# Volta-Interface-SCH_SH2__02.net
KiCad netlist of a schematic drawn in Altium Designer
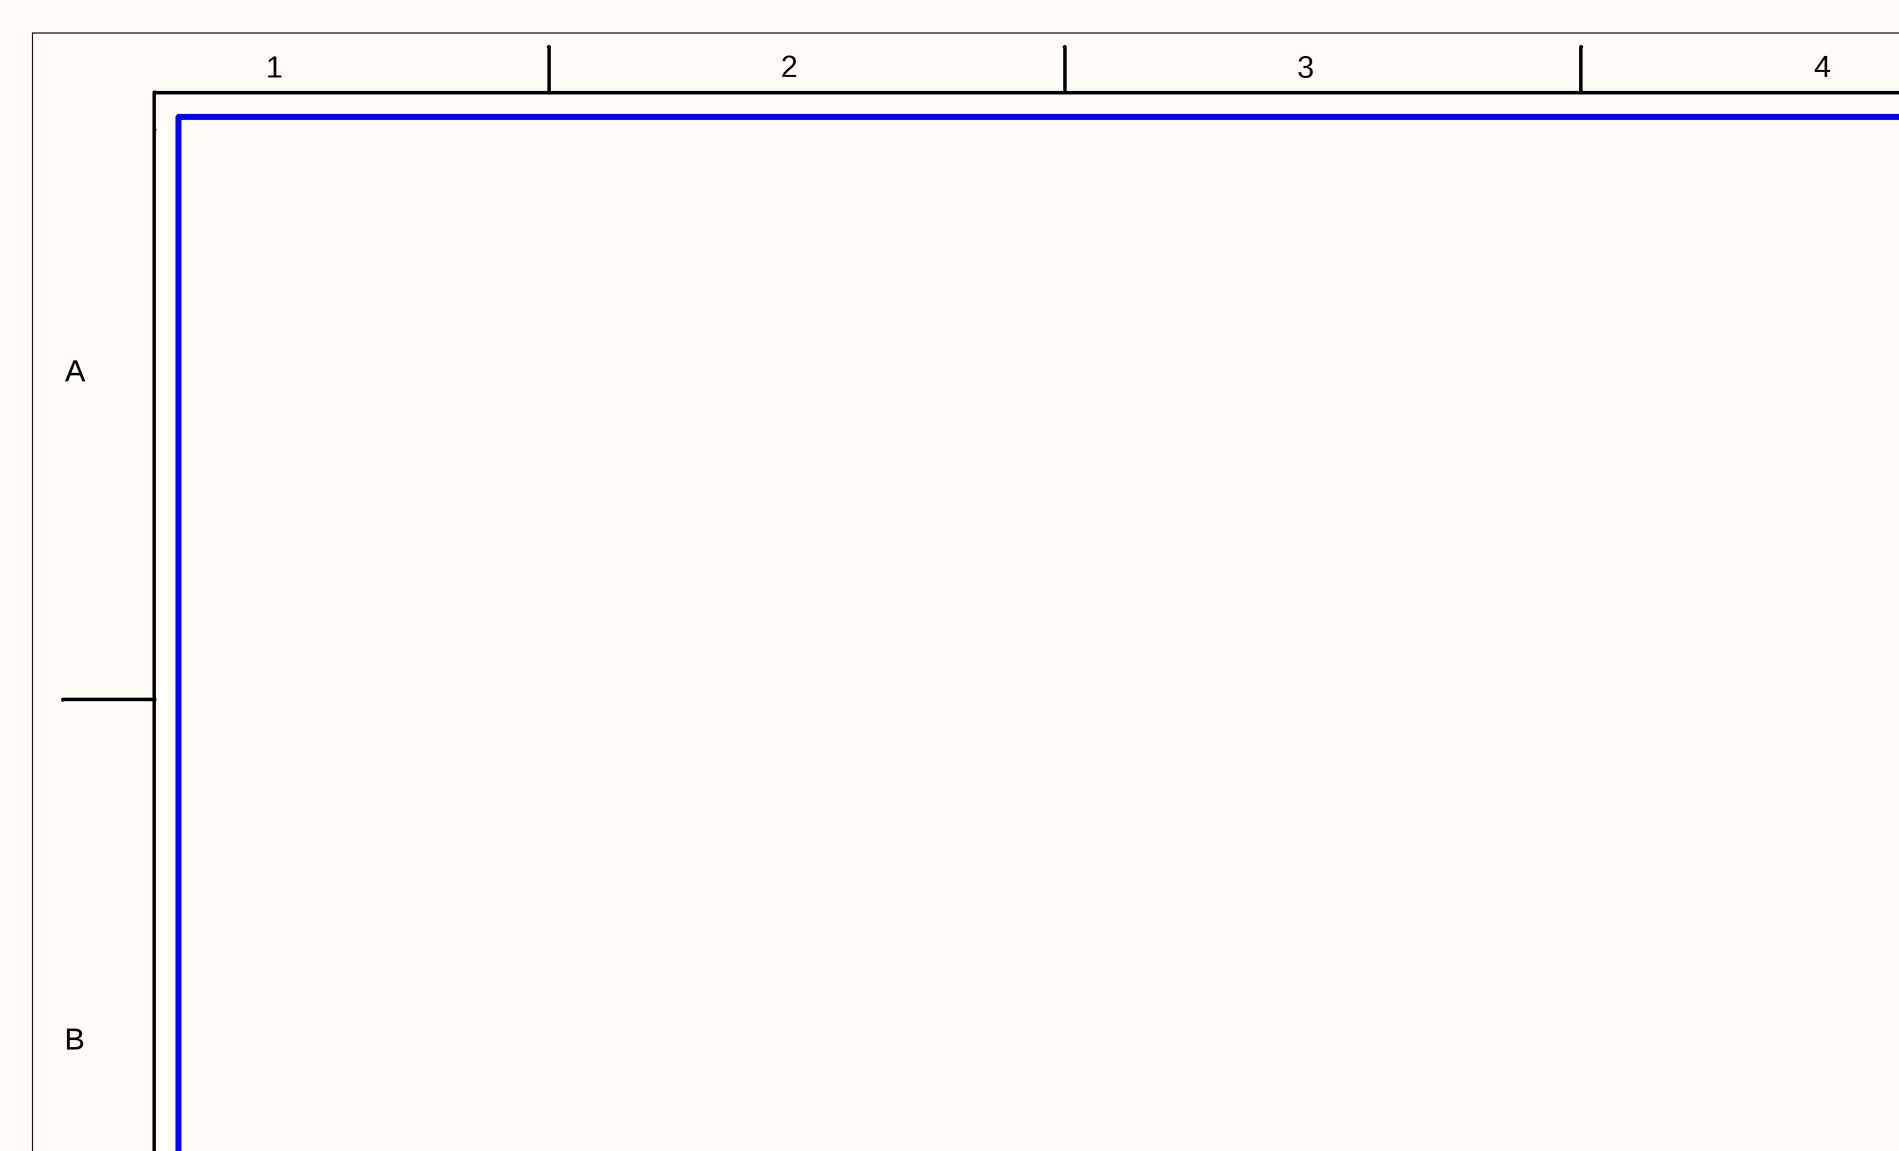
[diagram p0: Volta-Interface-SCH_SH2_(02).SchDoc, top left]
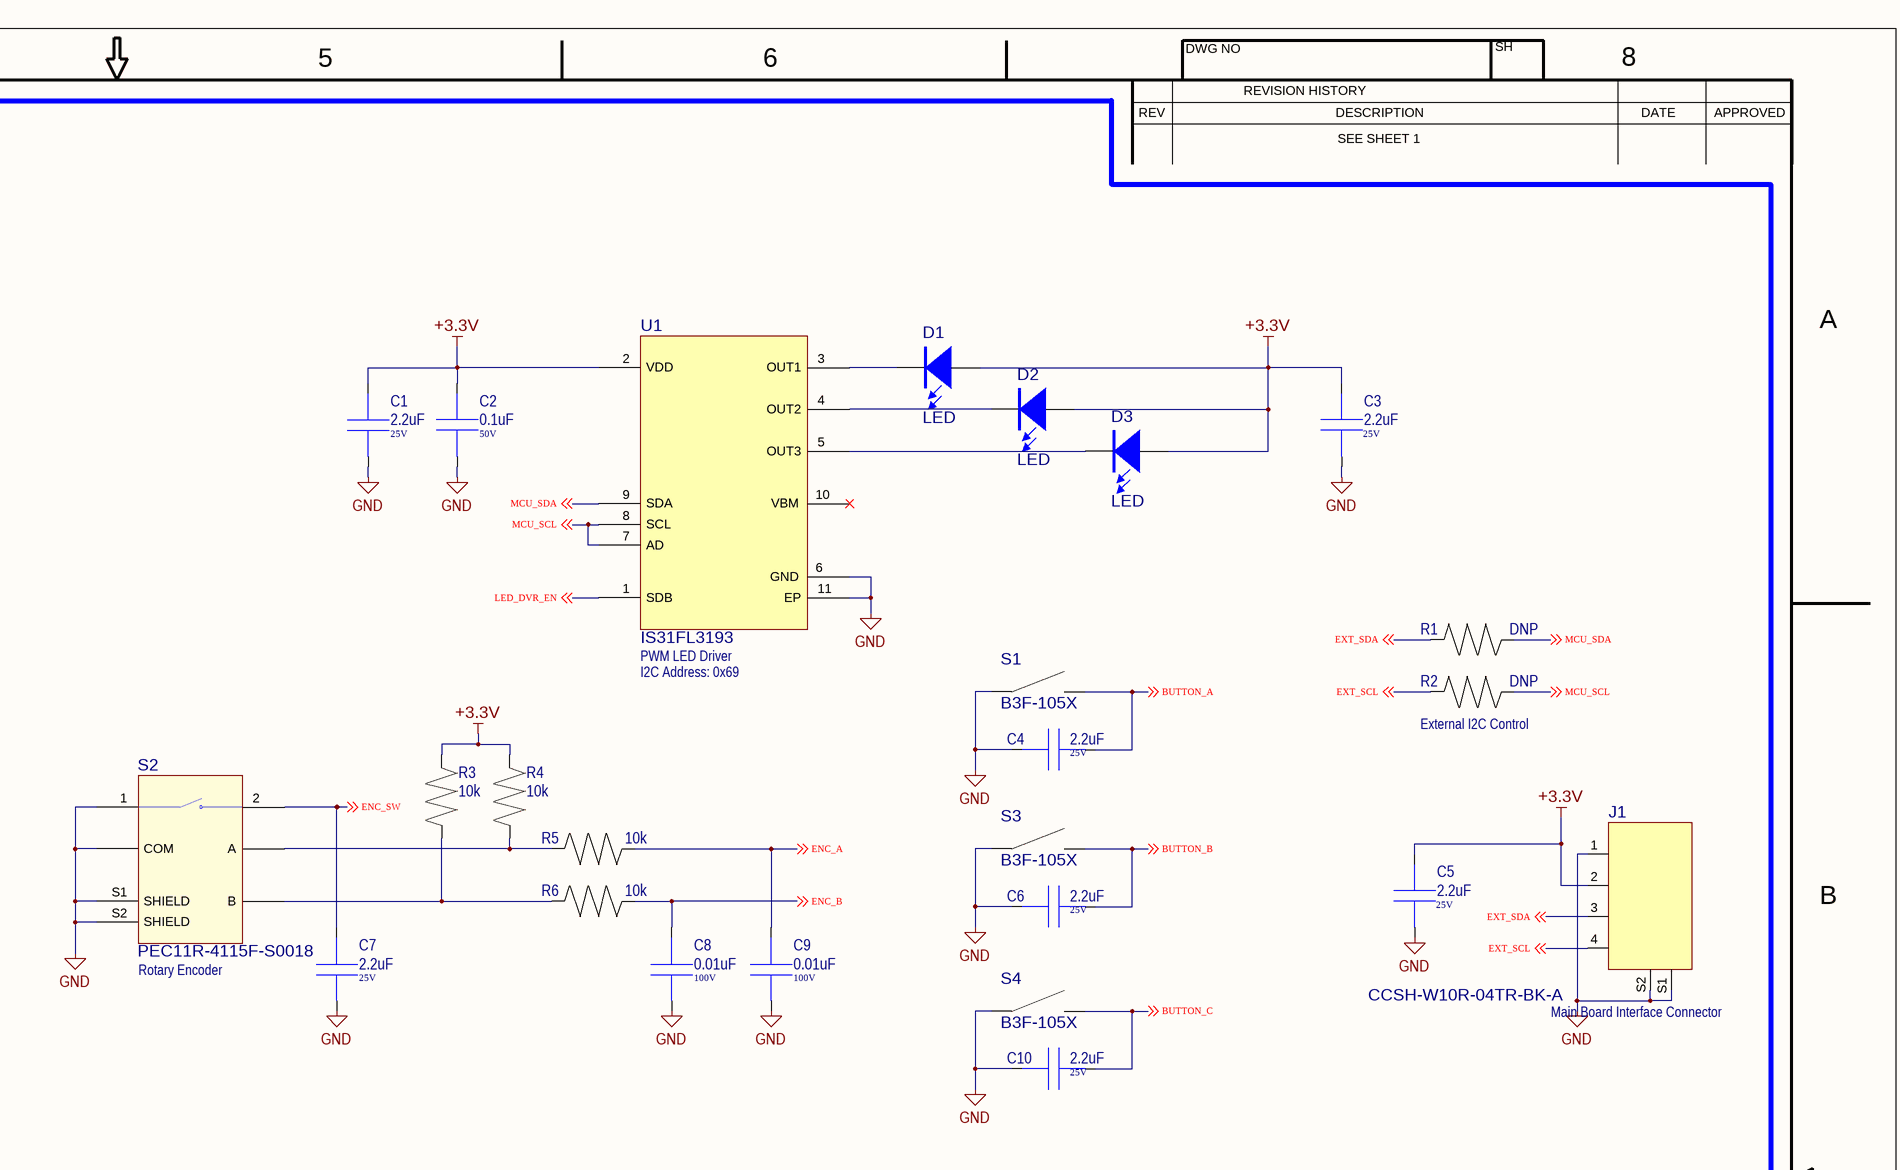
[diagram p1: Volta-Interface-SCH_SH2_(02).SchDoc, top right]
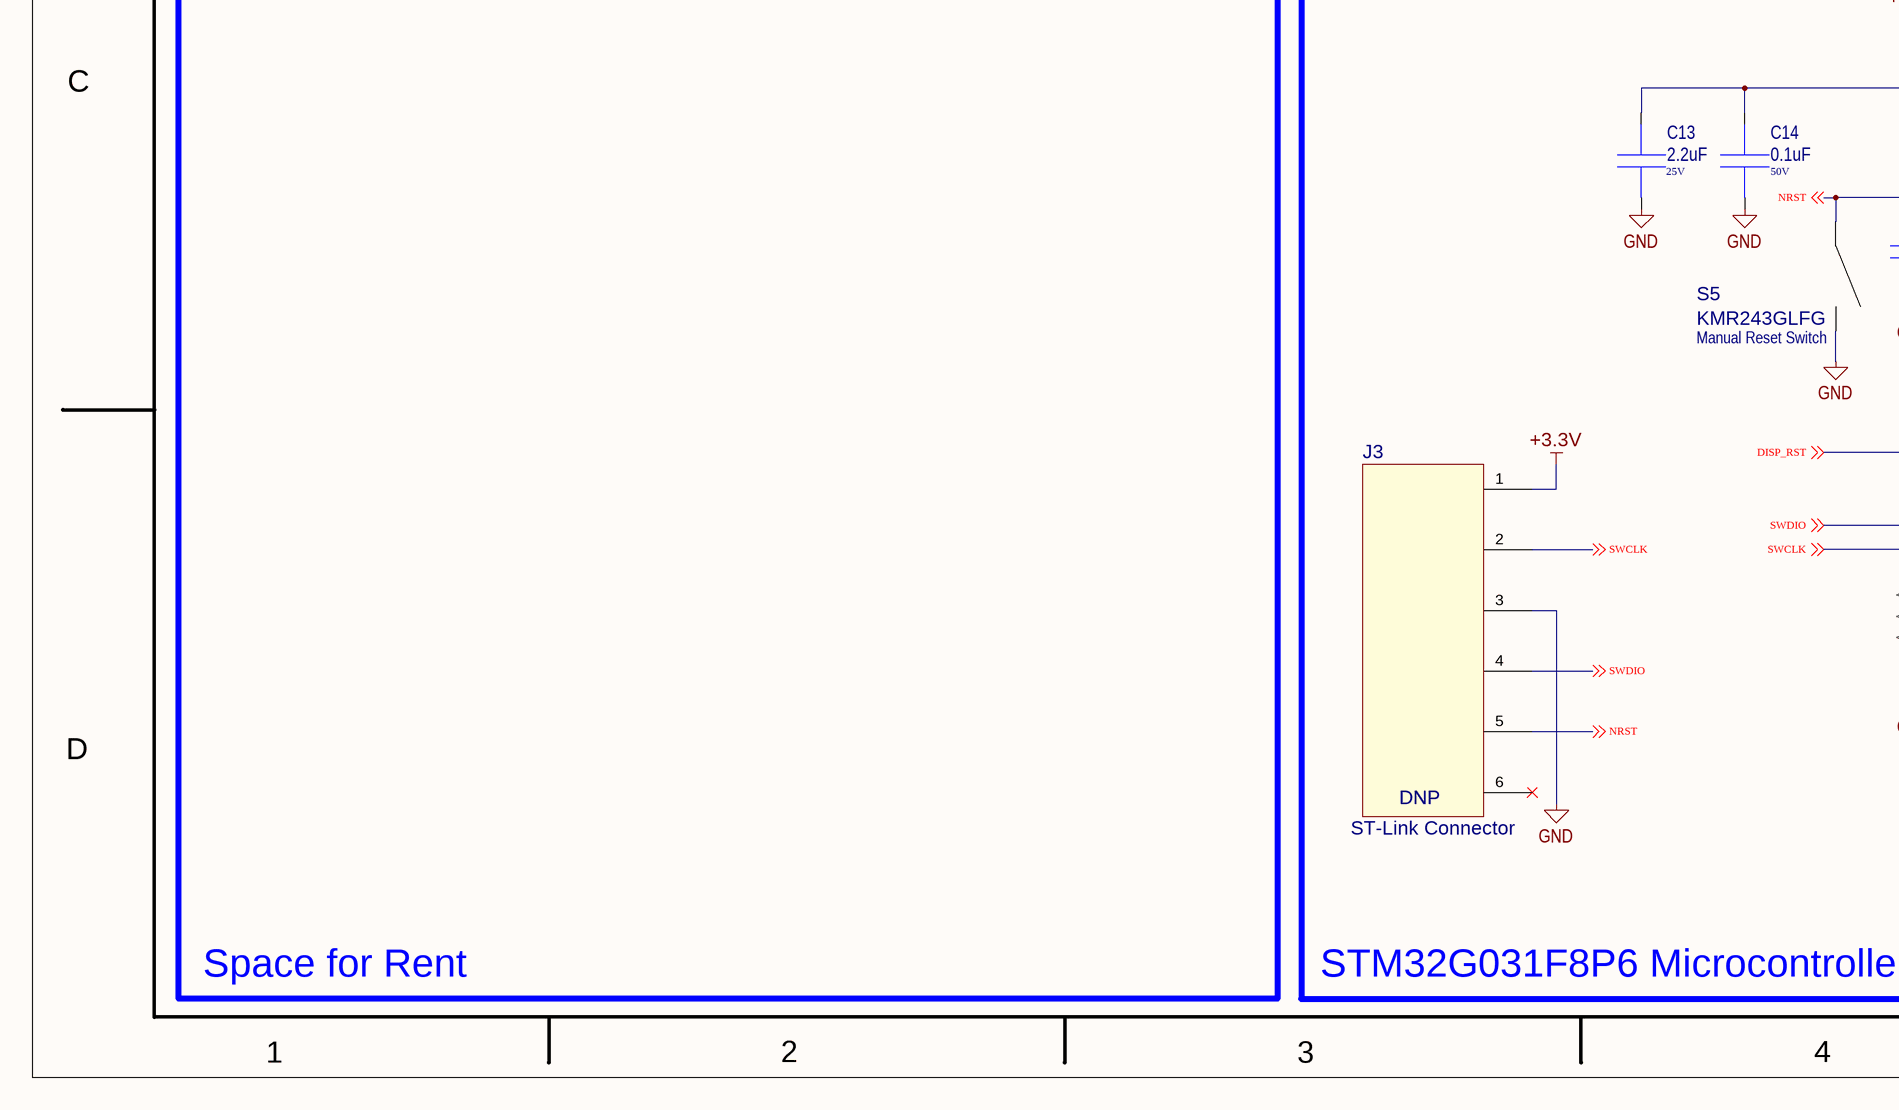
[diagram p2: Volta-Interface-SCH_SH2_(02).SchDoc, bottom left]
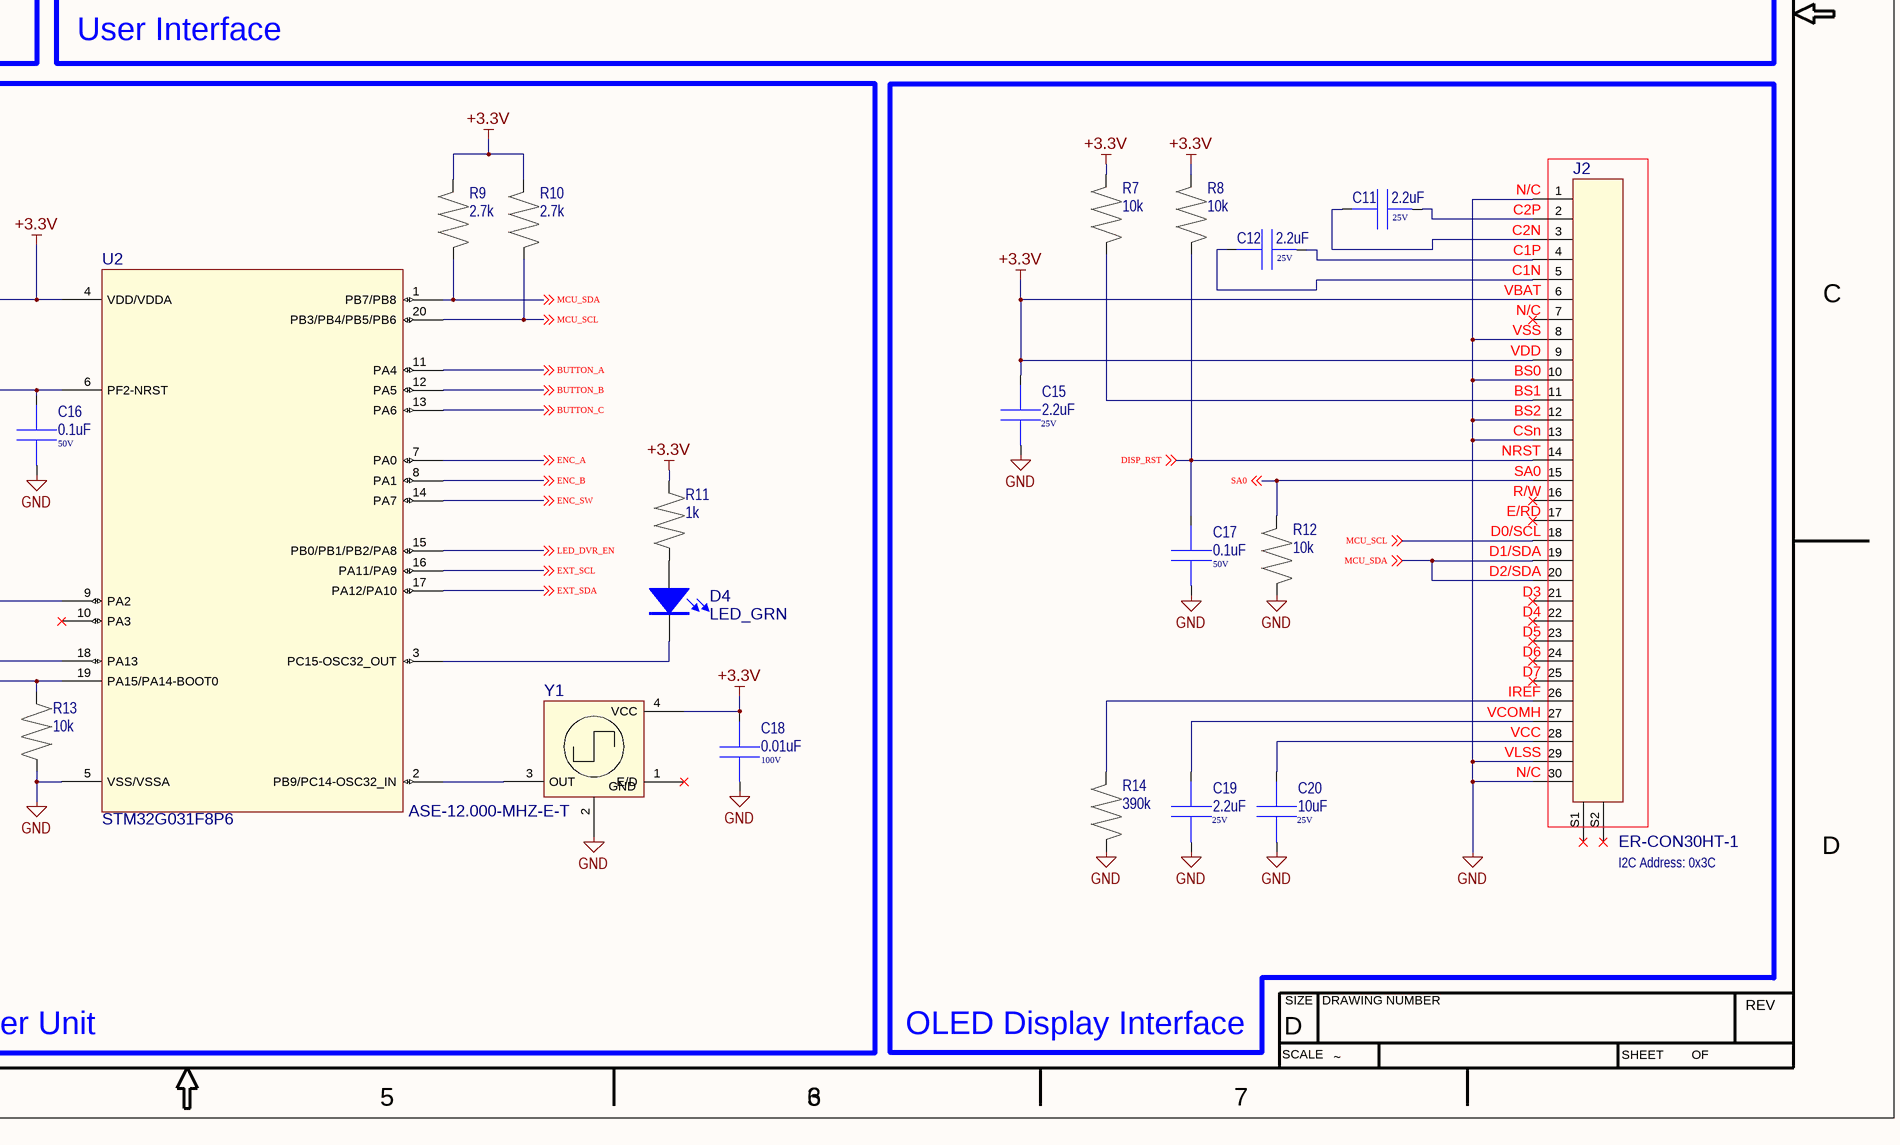
[diagram p3: Volta-Interface-SCH_SH2_(02).SchDoc, bottom right]

(export (version "E")
  (design (tool "Eeschema 10.0.6"))
  (components
    (comp (ref "C1")
      (value "2.2uF")
      (footprint "0402")
      (description "Multilayer Ceramic Capacitors MLCC - SMD/SMT 2.2UF 25V 10% 0402")
      (fields
        (field (name "PART NUMBER") "GRM155R61E225KE11D")
        (field (name "MANUFACTURER") "Murata Electronics")
        (field (name "VOLTAGE") "25V")
      )
      (libsource (lib "CAPACITORS") (part "CAP"))
    )
    (comp (ref "C2")
      (value "0.1uF")
      (footprint "0402")
      (description "CAP CER 0.1UF 50V X7R 0402")
      (fields
        (field (name "PART NUMBER") "UMK105B7104KVHF")
        (field (name "MANUFACTURER") "Taiyo Yuden")
        (field (name "VOLTAGE") "50V")
      )
      (libsource (lib "CAPACITORS") (part "CAP"))
    )
    (comp (ref "C3")
      (value "2.2uF")
      (footprint "0402")
      (description "Multilayer Ceramic Capacitors MLCC - SMD/SMT 2.2UF 25V 10% 0402")
      (fields
        (field (name "PART NUMBER") "GRM155R61E225KE11D")
        (field (name "MANUFACTURER") "Murata Electronics")
        (field (name "VOLTAGE") "25V")
      )
      (libsource (lib "CAPACITORS") (part "CAP"))
    )
    (comp (ref "C4")
      (value "2.2uF")
      (footprint "0402")
      (description "Multilayer Ceramic Capacitors MLCC - SMD/SMT 2.2UF 25V 10% 0402")
      (fields
        (field (name "PART NUMBER") "GRM155R61E225KE11D")
        (field (name "MANUFACTURER") "Murata Electronics")
        (field (name "VOLTAGE") "25V")
      )
      (libsource (lib "CAPACITORS") (part "CAP"))
    )
    (comp (ref "C5")
      (value "2.2uF")
      (footprint "0402")
      (description "Multilayer Ceramic Capacitors MLCC - SMD/SMT 2.2UF 25V 10% 0402")
      (fields
        (field (name "PART NUMBER") "GRM155R61E225KE11D")
        (field (name "MANUFACTURER") "Murata Electronics")
        (field (name "VOLTAGE") "25V")
      )
      (libsource (lib "CAPACITORS") (part "CAP"))
    )
    (comp (ref "C6")
      (value "2.2uF")
      (footprint "0402")
      (description "Multilayer Ceramic Capacitors MLCC - SMD/SMT 2.2UF 25V 10% 0402")
      (fields
        (field (name "PART NUMBER") "GRM155R61E225KE11D")
        (field (name "MANUFACTURER") "Murata Electronics")
        (field (name "VOLTAGE") "25V")
      )
      (libsource (lib "CAPACITORS") (part "CAP"))
    )
    (comp (ref "C7")
      (value "2.2uF")
      (footprint "0402")
      (description "Multilayer Ceramic Capacitors MLCC - SMD/SMT 2.2UF 25V 10% 0402")
      (fields
        (field (name "PART NUMBER") "GRM155R61E225KE11D")
        (field (name "MANUFACTURER") "Murata Electronics")
        (field (name "VOLTAGE") "25V")
      )
      (libsource (lib "CAPACITORS") (part "CAP"))
    )
    (comp (ref "C8")
      (value "0.01uF")
      (footprint "0402")
      (description "CAP CER 0.01UF 100V X7R 0402")
      (fields
        (field (name "PART NUMBER") "HMR105B7103MV-F")
        (field (name "MANUFACTURER") "Taiyo Yuden")
        (field (name "VOLTAGE") "100V")
      )
      (libsource (lib "CAPACITORS") (part "CAP"))
    )
    (comp (ref "C9")
      (value "0.01uF")
      (footprint "0402")
      (description "CAP CER 0.01UF 100V X7R 0402")
      (fields
        (field (name "PART NUMBER") "HMR105B7103MV-F")
        (field (name "MANUFACTURER") "Taiyo Yuden")
        (field (name "VOLTAGE") "100V")
      )
      (libsource (lib "CAPACITORS") (part "CAP"))
    )
    (comp (ref "C10")
      (value "2.2uF")
      (footprint "0402")
      (description "Multilayer Ceramic Capacitors MLCC - SMD/SMT 2.2UF 25V 10% 0402")
      (fields
        (field (name "PART NUMBER") "GRM155R61E225KE11D")
        (field (name "MANUFACTURER") "Murata Electronics")
        (field (name "VOLTAGE") "25V")
      )
      (libsource (lib "CAPACITORS") (part "CAP"))
    )
    (comp (ref "C11")
      (value "2.2uF")
      (footprint "0402")
      (description "CAP CER 10UF 10V X6S 0603")
      (fields
        (field (name "PART NUMBER") "GRM188C81A106MA73D")
        (field (name "MANUFACTURER") "Murata Electronics")
        (field (name "VOLTAGE") "25V")
      )
      (libsource (lib "CAPACITORS") (part "CAP"))
    )
    (comp (ref "C12")
      (value "2.2uF")
      (footprint "0402")
      (description "CAP CER 10UF 10V X6S 0603")
      (fields
        (field (name "PART NUMBER") "GRM188C81A106MA73D")
        (field (name "MANUFACTURER") "Murata Electronics")
        (field (name "VOLTAGE") "25V")
      )
      (libsource (lib "CAPACITORS") (part "CAP"))
    )
    (comp (ref "C13")
      (value "2.2uF")
      (footprint "0402")
      (description "Multilayer Ceramic Capacitors MLCC - SMD/SMT 2.2UF 25V 10% 0402")
      (fields
        (field (name "PART NUMBER") "GRM155R61E225KE11D")
        (field (name "MANUFACTURER") "Murata Electronics")
        (field (name "VOLTAGE") "25V")
      )
      (libsource (lib "CAPACITORS") (part "CAP"))
    )
    (comp (ref "C14")
      (value "0.1uF")
      (footprint "0402")
      (description "CAP CER 0.1UF 50V X7R 0402")
      (fields
        (field (name "PART NUMBER") "UMK105B7104KVHF")
        (field (name "MANUFACTURER") "Taiyo Yuden")
        (field (name "VOLTAGE") "50V")
      )
      (libsource (lib "CAPACITORS") (part "CAP"))
    )
    (comp (ref "C15")
      (value "2.2uF")
      (footprint "0402")
      (description "CAP CER 10UF 10V X6S 0603")
      (fields
        (field (name "PART NUMBER") "GRM188C81A106MA73D")
        (field (name "MANUFACTURER") "Murata Electronics")
        (field (name "VOLTAGE") "25V")
      )
      (libsource (lib "CAPACITORS") (part "CAP"))
    )
    (comp (ref "C16")
      (value "0.1uF")
      (footprint "0402")
      (description "CAP CER 0.1UF 50V X7R 0402")
      (fields
        (field (name "PART NUMBER") "UMK105B7104KVHF")
        (field (name "MANUFACTURER") "Taiyo Yuden")
        (field (name "VOLTAGE") "50V")
      )
      (libsource (lib "CAPACITORS") (part "CAP"))
    )
    (comp (ref "C17")
      (value "0.1uF")
      (footprint "0402")
      (description "CAP CER 0.1UF 50V X7R 0402")
      (fields
        (field (name "PART NUMBER") "UMK105B7104KVHF")
        (field (name "MANUFACTURER") "Taiyo Yuden")
        (field (name "VOLTAGE") "50V")
      )
      (libsource (lib "CAPACITORS") (part "CAP"))
    )
    (comp (ref "C18")
      (value "0.01uF")
      (footprint "0402")
      (description "CAP CER 0.01UF 100V X7R 0402")
      (fields
        (field (name "PART NUMBER") "HMR105B7103MV-F")
        (field (name "MANUFACTURER") "Taiyo Yuden")
        (field (name "VOLTAGE") "100V")
      )
      (libsource (lib "CAPACITORS") (part "CAP"))
    )
    (comp (ref "C19")
      (value "2.2uF")
      (footprint "0402")
      (description "CAP CER 10UF 10V X6S 0603")
      (fields
        (field (name "PART NUMBER") "GRM188C81A106MA73D")
        (field (name "MANUFACTURER") "Murata Electronics")
        (field (name "VOLTAGE") "25V")
      )
      (libsource (lib "CAPACITORS") (part "CAP"))
    )
    (comp (ref "C20")
      (value "10uF")
      (footprint "0402")
      (description "CAP CER 10UF 10V X6S 0603")
      (fields
        (field (name "PART NUMBER") "GRM188C81A106MA73D")
        (field (name "MANUFACTURER") "Murata Electronics")
        (field (name "VOLTAGE") "25V")
      )
      (libsource (lib "CAPACITORS") (part "CAP"))
    )
    (comp (ref "D1") (value "LED") (footprint "1206_LED") (libsource (lib "SEMICONDUCTORS") (part "LED")))
    (comp (ref "D2") (value "LED") (footprint "1206_LED") (libsource (lib "SEMICONDUCTORS") (part "LED")))
    (comp (ref "D3") (value "LED") (footprint "1206_LED") (libsource (lib "SEMICONDUCTORS") (part "LED")))
    (comp (ref "D4")
      (value "LED_GRN")
      (footprint "0603_LED_Red")
      (description "Standard LEDs - SMD HE Red 645 nm Water Clear")
      (fields (field (name "PART NUMBER") "SM0603HCL") (field (name "MANUFACTURER") "Bivar"))
      (libsource (lib "SEMICONDUCTORS") (part "LED_Red"))
    )
    (comp (ref "J1")
      (value "CCSH-W10R-04TR-BK-A")
      (footprint "PCBComponent_1")
      (fields (field (name "MANUFACTURER") "JST"))
      (libsource (lib "CCSH-W10R-04TR-BK-A") (part "CCSH-W10R-04TR-BK-A"))
    )
    (comp (ref "J2")
      (value "ER-CON30HT-1")
      (footprint "ER-CON30HT-1")
      (description "30 PINS 0.5 PITCH SMD TOP CONTACT CONN")
      (fields (field (name "MANUFACTURER") "EastRising Technology"))
      (libsource (lib "ER-CON30HT-1") (part "ER-CON30HT-1"))
    )
    (comp (ref "J3")
      (value "DNP")
      (footprint "801-93-006-10-012000")
      (description "CONN SOCKET STRIP LOPRO 6POS")
      (fields (field (name "MANUFACTURER") "Mill-Max") (field (name "PART NUMBER") "801-93-006-10-012000"))
      (libsource (lib "Connectors") (part "801-93-006-10-012000"))
    )
    (comp (ref "R1")
      (value "DNP")
      (footprint "0402")
      (description "Thick Film Resistors - SMD 1/16watt 0ohm Commercial Use")
      (fields (field (name "PART NUMBER") "CRCW04020000Z0EDC") (field (name "MANUFACTURER") "Vishay / Dale"))
      (libsource (lib "RESISTORS") (part "RES"))
    )
    (comp (ref "R2")
      (value "DNP")
      (footprint "0402")
      (description "Thick Film Resistors - SMD 1/16watt 0ohm Commercial Use")
      (fields (field (name "PART NUMBER") "CRCW04020000Z0EDC") (field (name "MANUFACTURER") "Vishay / Dale"))
      (libsource (lib "RESISTORS") (part "RES"))
    )
    (comp (ref "R3")
      (value "10k")
      (footprint "0402")
      (description "Thick Film Resistors - SMD 10K OHM 1%")
      (fields (field (name "PART NUMBER") "CR0402-FX-1002GLF") (field (name "MANUFACTURER") "Bourns"))
      (libsource (lib "RESISTORS") (part "RES"))
    )
    (comp (ref "R4")
      (value "10k")
      (footprint "0402")
      (description "Thick Film Resistors - SMD 10K OHM 1%")
      (fields (field (name "PART NUMBER") "CR0402-FX-1002GLF") (field (name "MANUFACTURER") "Bourns"))
      (libsource (lib "RESISTORS") (part "RES"))
    )
    (comp (ref "R5")
      (value "10k")
      (footprint "0402")
      (description "Thick Film Resistors - SMD 10K OHM 1%")
      (fields (field (name "PART NUMBER") "CR0402-FX-1002GLF") (field (name "MANUFACTURER") "Bourns"))
      (libsource (lib "RESISTORS") (part "RES"))
    )
    (comp (ref "R6")
      (value "10k")
      (footprint "0402")
      (description "Thick Film Resistors - SMD 10K OHM 1%")
      (fields (field (name "PART NUMBER") "CR0402-FX-1002GLF") (field (name "MANUFACTURER") "Bourns"))
      (libsource (lib "RESISTORS") (part "RES"))
    )
    (comp (ref "R7")
      (value "10k")
      (footprint "0402")
      (description "Thick Film Resistors - SMD 0603 5.1Kohm 5% High Voltage")
      (fields (field (name "PART NUMBER") "KTR03EZPJ512") (field (name "MANUFACTURER") "ROHM Semiconductor"))
      (libsource (lib "RESISTORS") (part "RES"))
    )
    (comp (ref "R8")
      (value "10k")
      (footprint "0402")
      (description "Thick Film Resistors - SMD 0603 5.1Kohm 5% High Voltage")
      (fields (field (name "PART NUMBER") "KTR03EZPJ512") (field (name "MANUFACTURER") "ROHM Semiconductor"))
      (libsource (lib "RESISTORS") (part "RES"))
    )
    (comp (ref "R9")
      (value "2.7k")
      (footprint "0402")
      (description "Thick Film Resistors - SMD 0402 2.7Kohms 1% AEC-Q200")
      (fields (field (name "PART NUMBER") "ERJ-2RKF2701X") (field (name "MANUFACTURER") "Panasonic"))
      (libsource (lib "RESISTORS") (part "RES"))
    )
    (comp (ref "R10")
      (value "2.7k")
      (footprint "0402")
      (description "Thick Film Resistors - SMD 0402 2.7Kohms 1% AEC-Q200")
      (fields (field (name "PART NUMBER") "ERJ-2RKF2701X") (field (name "MANUFACTURER") "Panasonic"))
      (libsource (lib "RESISTORS") (part "RES"))
    )
    (comp (ref "R11")
      (value "1k")
      (footprint "0402")
      (description "Thick Film Resistors - SMD ResA 0402 1k 1% 63mW TC100")
      (fields (field (name "PART NUMBER") "CR0402AFX-1001GLF") (field (name "MANUFACTURER") "Bourns"))
      (libsource (lib "RESISTORS") (part "RES"))
    )
    (comp (ref "R12")
      (value "10k")
      (footprint "0402")
      (description "Thick Film Resistors - SMD 0603 5.1Kohm 5% High Voltage")
      (fields (field (name "PART NUMBER") "KTR03EZPJ512") (field (name "MANUFACTURER") "ROHM Semiconductor"))
      (libsource (lib "RESISTORS") (part "RES"))
    )
    (comp (ref "R13")
      (value "10k")
      (footprint "0402")
      (description "Thick Film Resistors - SMD 10K OHM 1%")
      (fields (field (name "PART NUMBER") "CR0402-FX-1002GLF") (field (name "MANUFACTURER") "Bourns"))
      (libsource (lib "RESISTORS") (part "RES"))
    )
    (comp (ref "R14")
      (value "390k")
      (footprint "0402")
      (description "Thick Film Resistors - SMD 0603 5.1Kohm 5% High Voltage")
      (fields (field (name "PART NUMBER") "KTR03EZPJ512") (field (name "MANUFACTURER") "ROHM Semiconductor"))
      (libsource (lib "RESISTORS") (part "RES"))
    )
    (comp (ref "S1")
      (value "B3F-105X")
      (footprint "B3F-105X")
      (description "SWITCH TACTILE SPST-NO 0.05A 24V")
      (fields (field (name "MANUFACTURER") "Omron Electronics Inc-EMC Div"))
      (libsource (lib "B3F-105X") (part "B3F-105X"))
    )
    (comp (ref "S2")
      (value "PEC11R-4115F-S0018")
      (footprint "PEC11R-4xxxF-Sxxxx")
      (description "ROTARY ENCODER MECHANICAL XXPPR")
      (fields (field (name "MANUFACTURER") "Bourns"))
      (libsource (lib "PEC11R-4xxxF-Sxxxx") (part "PEC11R-4xxxF-Sxxxx"))
    )
    (comp (ref "S3")
      (value "B3F-105X")
      (footprint "B3F-105X")
      (description "SWITCH TACTILE SPST-NO 0.05A 24V")
      (fields (field (name "MANUFACTURER") "Omron Electronics Inc-EMC Div"))
      (libsource (lib "B3F-105X") (part "B3F-105X"))
    )
    (comp (ref "S4")
      (value "B3F-105X")
      (footprint "B3F-105X")
      (description "SWITCH TACTILE SPST-NO 0.05A 24V")
      (fields (field (name "MANUFACTURER") "Omron Electronics Inc-EMC Div"))
      (libsource (lib "B3F-105X") (part "B3F-105X"))
    )
    (comp (ref "S5")
      (value "KMR243GLFG")
      (footprint "KMR 2 Series")
      (description "Tactile Switch SPST-NO Top Actuated Surface Mount")
      (fields (field (name "MANUFACTURER") "C&K") (field (name "PART NUMBER") "KMR243GFLG"))
      (libsource (lib "KMR2 Series") (part "KMR 2 Series"))
    )
    (comp (ref "U1")
      (value "IS31FL3193")
      (footprint "DFN-10")
      (description "IC LED DRIVER LINEAR 42MA 10DFN")
      (fields
        (field (name "MANUFACTURER") "Lumissil Microsystems")
        (field (name "PART NUMBER") "IS31FL3193-DLS2-TR")
      )
      (libsource (lib "IS31FL3193") (part "IS31FL3193"))
    )
    (comp (ref "U2")
      (value "STM32G031F8P6")
      (footprint "TSSOP-20")
      (description "IC MCU 32BIT 64KB FLASH 20TSSOP")
      (fields (field (name "MANUFACTURER") "STMicroelectronics"))
      (libsource (lib "STM32G031Fxxx") (part "STM32G031F6P6"))
    )
    (comp (ref "Y1")
      (value "ASE-12.000-MHZ-E-T")
      (footprint "ASE-XXXXX-X-X-X")
      (description "OSC XO 12.000MHZ CMOS SMD")
      (fields (field (name "MANUFACTURER") "Abracon"))
      (libsource (lib "Oscillators") (part "ASE-XXXXX-MHZ-X-X"))
    )
  )
  (nets
    (net (code "1") (name "+3.3V") (class "Default")
      (node (ref "C1") (pin "2") (pinfunction "2_2") (pintype "passive"))
      (node (ref "C13") (pin "2") (pinfunction "2_2") (pintype "passive"))
      (node (ref "C14") (pin "2") (pinfunction "2_2") (pintype "passive"))
      (node (ref "C15") (pin "2") (pinfunction "2_2") (pintype "passive"))
      (node (ref "C18") (pin "2") (pinfunction "2_2") (pintype "passive"))
      (node (ref "C2") (pin "2") (pinfunction "2_2") (pintype "passive"))
      (node (ref "C3") (pin "2") (pinfunction "2_2") (pintype "passive"))
      (node (ref "C5") (pin "2") (pinfunction "2_2") (pintype "passive"))
      (node (ref "D1") (pin "1") (pinfunction "A_1") (pintype "passive"))
      (node (ref "D2") (pin "1") (pinfunction "A_1") (pintype "passive"))
      (node (ref "D3") (pin "1") (pinfunction "A_1") (pintype "passive"))
      (node (ref "J1") (pin "2") (pinfunction "2_2") (pintype "passive"))
      (node (ref "J2") (pin "6") (pinfunction "6_6") (pintype "passive"))
      (node (ref "J2") (pin "9") (pinfunction "9_9") (pintype "passive"))
      (node (ref "J3") (pin "1") (pinfunction "1_1") (pintype "passive"))
      (node (ref "R10") (pin "2") (pinfunction "2_2") (pintype "passive"))
      (node (ref "R11") (pin "2") (pinfunction "2_2") (pintype "passive"))
      (node (ref "R3") (pin "1") (pinfunction "1_1") (pintype "passive"))
      (node (ref "R4") (pin "1") (pinfunction "1_1") (pintype "passive"))
      (node (ref "R7") (pin "2") (pinfunction "2_2") (pintype "passive"))
      (node (ref "R8") (pin "2") (pinfunction "2_2") (pintype "passive"))
      (node (ref "R9") (pin "2") (pinfunction "2_2") (pintype "passive"))
      (node (ref "U1") (pin "2") (pinfunction "VDD_2") (pintype "passive"))
      (node (ref "U2") (pin "4") (pinfunction "VDD/VDDA_4") (pintype "power_in"))
      (node (ref "Y1") (pin "4") (pinfunction "VCC_4") (pintype "power_in"))
    )
    (net (code "2") (name "BUTTON_A") (class "Default")
      (node (ref "C4") (pin "1") (pinfunction "1_1") (pintype "passive"))
      (node (ref "S1") (pin "2") (pinfunction "2_2") (pintype "passive"))
      (node (ref "U2") (pin "11") (pinfunction "PA4_11") (pintype "bidirectional"))
    )
    (net (code "3") (name "BUTTON_B") (class "Default")
      (node (ref "C6") (pin "1") (pinfunction "1_1") (pintype "passive"))
      (node (ref "S3") (pin "2") (pinfunction "2_2") (pintype "passive"))
      (node (ref "U2") (pin "12") (pinfunction "PA5_12") (pintype "bidirectional"))
    )
    (net (code "4") (name "BUTTON_C") (class "Default")
      (node (ref "C10") (pin "1") (pinfunction "1_1") (pintype "passive"))
      (node (ref "S4") (pin "2") (pinfunction "2_2") (pintype "passive"))
      (node (ref "U2") (pin "13") (pinfunction "PA6_13") (pintype "bidirectional"))
    )
    (net (code "5") (name "DISP_RST") (class "Default")
      (node (ref "C17") (pin "2") (pinfunction "2_2") (pintype "passive"))
      (node (ref "J2") (pin "14") (pinfunction "14_14") (pintype "passive"))
      (node (ref "R8") (pin "1") (pinfunction "1_1") (pintype "passive"))
      (node (ref "U2") (pin "9") (pinfunction "PA2_9") (pintype "bidirectional"))
    )
    (net (code "6") (name "ENC_A") (class "Default")
      (node (ref "C9") (pin "2") (pinfunction "2_2") (pintype "passive"))
      (node (ref "R5") (pin "2") (pinfunction "2_2") (pintype "passive"))
      (node (ref "U2") (pin "7") (pinfunction "PA0_7") (pintype "bidirectional"))
    )
    (net (code "7") (name "ENC_B") (class "Default")
      (node (ref "C8") (pin "2") (pinfunction "2_2") (pintype "passive"))
      (node (ref "R6") (pin "2") (pinfunction "2_2") (pintype "passive"))
      (node (ref "U2") (pin "8") (pinfunction "PA1_8") (pintype "bidirectional"))
    )
    (net (code "8") (name "ENC_SW") (class "Default")
      (node (ref "C7") (pin "2") (pinfunction "2_2") (pintype "passive"))
      (node (ref "S2") (pin "2") (pinfunction "2_2") (pintype "passive"))
      (node (ref "U2") (pin "14") (pinfunction "PA7_14") (pintype "bidirectional"))
    )
    (net (code "9") (name "EXT_SCL") (class "Default")
      (node (ref "J1") (pin "4") (pinfunction "4_4") (pintype "passive"))
      (node (ref "R2") (pin "2") (pinfunction "2_2") (pintype "passive"))
      (node (ref "U2") (pin "16") (pinfunction "PA11/PA9_16") (pintype "bidirectional"))
    )
    (net (code "10") (name "EXT_SDA") (class "Default")
      (node (ref "J1") (pin "3") (pinfunction "3_3") (pintype "passive"))
      (node (ref "R1") (pin "2") (pinfunction "2_2") (pintype "passive"))
      (node (ref "U2") (pin "17") (pinfunction "PA12/PA10_17") (pintype "bidirectional"))
    )
    (net (code "11") (name "GND") (class "Default")
      (node (ref "C1") (pin "1") (pinfunction "1_1") (pintype "passive"))
      (node (ref "C10") (pin "2") (pinfunction "2_2") (pintype "passive"))
      (node (ref "C13") (pin "1") (pinfunction "1_1") (pintype "passive"))
      (node (ref "C14") (pin "1") (pinfunction "1_1") (pintype "passive"))
      (node (ref "C15") (pin "1") (pinfunction "1_1") (pintype "passive"))
      (node (ref "C16") (pin "1") (pinfunction "1_1") (pintype "passive"))
      (node (ref "C17") (pin "1") (pinfunction "1_1") (pintype "passive"))
      (node (ref "C18") (pin "1") (pinfunction "1_1") (pintype "passive"))
      (node (ref "C19") (pin "1") (pinfunction "1_1") (pintype "passive"))
      (node (ref "C2") (pin "1") (pinfunction "1_1") (pintype "passive"))
      (node (ref "C20") (pin "1") (pinfunction "1_1") (pintype "passive"))
      (node (ref "C3") (pin "1") (pinfunction "1_1") (pintype "passive"))
      (node (ref "C4") (pin "2") (pinfunction "2_2") (pintype "passive"))
      (node (ref "C5") (pin "1") (pinfunction "1_1") (pintype "passive"))
      (node (ref "C6") (pin "2") (pinfunction "2_2") (pintype "passive"))
      (node (ref "C7") (pin "1") (pinfunction "1_1") (pintype "passive"))
      (node (ref "C8") (pin "1") (pinfunction "1_1") (pintype "passive"))
      (node (ref "C9") (pin "1") (pinfunction "1_1") (pintype "passive"))
      (node (ref "J1") (pin "1") (pinfunction "1_1") (pintype "passive"))
      (node (ref "J1") (pin "S1") (pinfunction "S1_S1") (pintype "passive"))
      (node (ref "J1") (pin "S2") (pinfunction "S2_S2") (pintype "passive"))
      (node (ref "J2") (pin "1") (pinfunction "1_1") (pintype "passive"))
      (node (ref "J2") (pin "10") (pinfunction "10_10") (pintype "passive"))
      (node (ref "J2") (pin "12") (pinfunction "12_12") (pintype "passive"))
      (node (ref "J2") (pin "13") (pinfunction "13_13") (pintype "passive"))
      (node (ref "J2") (pin "29") (pinfunction "29_29") (pintype "passive"))
      (node (ref "J2") (pin "30") (pinfunction "30_30") (pintype "passive"))
      (node (ref "J2") (pin "8") (pinfunction "8_8") (pintype "passive"))
      (node (ref "J3") (pin "3") (pinfunction "3_3") (pintype "passive"))
      (node (ref "R12") (pin "1") (pinfunction "1_1") (pintype "passive"))
      (node (ref "R13") (pin "2") (pinfunction "2_2") (pintype "passive"))
      (node (ref "R14") (pin "1") (pinfunction "1_1") (pintype "passive"))
      (node (ref "S1") (pin "1") (pinfunction "1_1") (pintype "passive"))
      (node (ref "S2") (pin "1") (pinfunction "1_1") (pintype "passive"))
      (node (ref "S2") (pin "COM") (pinfunction "COM_COM") (pintype "passive"))
      (node (ref "S2") (pin "S1") (pinfunction "SHIELD_S1") (pintype "passive"))
      (node (ref "S2") (pin "S2") (pinfunction "SHIELD_S2") (pintype "passive"))
      (node (ref "S3") (pin "1") (pinfunction "1_1") (pintype "passive"))
      (node (ref "S4") (pin "1") (pinfunction "1_1") (pintype "passive"))
      (node (ref "S5") (pin "2") (pinfunction "2_2") (pintype "passive"))
      (node (ref "U1") (pin "11") (pinfunction "EP_11") (pintype "passive"))
      (node (ref "U1") (pin "6") (pinfunction "GND_6") (pintype "passive"))
      (node (ref "U2") (pin "5") (pinfunction "VSS/VSSA_5") (pintype "power_in"))
      (node (ref "Y1") (pin "2") (pinfunction "GND_2") (pintype "passive"))
    )
    (net (code "12") (name "LED_DVR_EN") (class "Default")
      (node (ref "U1") (pin "1") (pinfunction "SDB_1") (pintype "passive"))
      (node (ref "U2") (pin "15") (pinfunction "PB0/PB1/PB2/PA8_15") (pintype "bidirectional"))
    )
    (net (code "13") (name "MCU_SCL") (class "Default")
      (node (ref "J2") (pin "18") (pinfunction "18_18") (pintype "passive"))
      (node (ref "R10") (pin "1") (pinfunction "1_1") (pintype "passive"))
      (node (ref "R2") (pin "1") (pinfunction "1_1") (pintype "passive"))
      (node (ref "U1") (pin "7") (pinfunction "AD_7") (pintype "passive"))
      (node (ref "U1") (pin "8") (pinfunction "SCL_8") (pintype "passive"))
      (node (ref "U2") (pin "20") (pinfunction "PB3/PB4/PB5/PB6_20") (pintype "bidirectional"))
    )
    (net (code "14") (name "MCU_SDA") (class "Default")
      (node (ref "J2") (pin "19") (pinfunction "19_19") (pintype "passive"))
      (node (ref "J2") (pin "20") (pinfunction "20_20") (pintype "passive"))
      (node (ref "R1") (pin "1") (pinfunction "1_1") (pintype "passive"))
      (node (ref "R9") (pin "1") (pinfunction "1_1") (pintype "passive"))
      (node (ref "U1") (pin "9") (pinfunction "SDA_9") (pintype "passive"))
      (node (ref "U2") (pin "1") (pinfunction "PB7/PB8_1") (pintype "bidirectional"))
    )
    (net (code "15") (name "NRST") (class "Default")
      (node (ref "C16") (pin "2") (pinfunction "2_2") (pintype "passive"))
      (node (ref "J3") (pin "5") (pinfunction "5_5") (pintype "passive"))
      (node (ref "S5") (pin "1") (pinfunction "1_1") (pintype "passive"))
      (node (ref "U2") (pin "6") (pinfunction "PF2-NRST_6") (pintype "passive"))
    )
    (net (code "16") (name "Net-(C11-Pad1)") (class "Default")
      (node (ref "C11") (pin "1") (pinfunction "1_1") (pintype "passive"))
      (node (ref "J2") (pin "2") (pinfunction "2_2") (pintype "passive"))
    )
    (net (code "17") (name "Net-(C11-Pad2)") (class "Default")
      (node (ref "C11") (pin "2") (pinfunction "2_2") (pintype "passive"))
      (node (ref "J2") (pin "3") (pinfunction "3_3") (pintype "passive"))
    )
    (net (code "18") (name "Net-(C12-Pad1)") (class "Default")
      (node (ref "C12") (pin "1") (pinfunction "1_1") (pintype "passive"))
      (node (ref "J2") (pin "4") (pinfunction "4_4") (pintype "passive"))
    )
    (net (code "19") (name "Net-(C12-Pad2)") (class "Default")
      (node (ref "C12") (pin "2") (pinfunction "2_2") (pintype "passive"))
      (node (ref "J2") (pin "5") (pinfunction "5_5") (pintype "passive"))
    )
    (net (code "20") (name "Net-(C19-Pad2)") (class "Default")
      (node (ref "C19") (pin "2") (pinfunction "2_2") (pintype "passive"))
      (node (ref "J2") (pin "27") (pinfunction "27_27") (pintype "passive"))
    )
    (net (code "21") (name "Net-(C20-Pad2)") (class "Default")
      (node (ref "C20") (pin "2") (pinfunction "2_2") (pintype "passive"))
      (node (ref "J2") (pin "28") (pinfunction "28_28") (pintype "passive"))
    )
    (net (code "22") (name "Net-(D1-K)") (class "Default")
      (node (ref "D1") (pin "2") (pinfunction "K_2") (pintype "passive"))
      (node (ref "U1") (pin "3") (pinfunction "OUT1_3") (pintype "passive"))
    )
    (net (code "23") (name "Net-(D2-K)") (class "Default")
      (node (ref "D2") (pin "2") (pinfunction "K_2") (pintype "passive"))
      (node (ref "U1") (pin "4") (pinfunction "OUT2_4") (pintype "passive"))
    )
    (net (code "24") (name "Net-(D3-K)") (class "Default")
      (node (ref "D3") (pin "2") (pinfunction "K_2") (pintype "passive"))
      (node (ref "U1") (pin "5") (pinfunction "OUT3_5") (pintype "passive"))
    )
    (net (code "25") (name "Net-(D4-A)") (class "Default")
      (node (ref "D4") (pin "1") (pinfunction "A_1") (pintype "passive"))
      (node (ref "R11") (pin "1") (pinfunction "1_1") (pintype "passive"))
    )
    (net (code "26") (name "Net-(D4-K)") (class "Default")
      (node (ref "D4") (pin "2") (pinfunction "K_2") (pintype "passive"))
      (node (ref "U2") (pin "3") (pinfunction "PC15-OSC32_OUT_3") (pintype "bidirectional"))
    )
    (net (code "27") (name "Net-(J2-Pad11)") (class "Default")
      (node (ref "J2") (pin "11") (pinfunction "11_11") (pintype "passive"))
      (node (ref "R7") (pin "1") (pinfunction "1_1") (pintype "passive"))
    )
    (net (code "28") (name "Net-(J2-Pad26)") (class "Default")
      (node (ref "J2") (pin "26") (pinfunction "26_26") (pintype "passive"))
      (node (ref "R14") (pin "2") (pinfunction "2_2") (pintype "passive"))
    )
    (net (code "29") (name "Net-(R3-Pad2)") (class "Default")
      (node (ref "R3") (pin "2") (pinfunction "2_2") (pintype "passive"))
      (node (ref "R6") (pin "1") (pinfunction "1_1") (pintype "passive"))
      (node (ref "S2") (pin "B") (pinfunction "B_B") (pintype "passive"))
    )
    (net (code "30") (name "Net-(R4-Pad2)") (class "Default")
      (node (ref "R4") (pin "2") (pinfunction "2_2") (pintype "passive"))
      (node (ref "R5") (pin "1") (pinfunction "1_1") (pintype "passive"))
      (node (ref "S2") (pin "A") (pinfunction "A_A") (pintype "passive"))
    )
    (net (code "31") (name "Net-(U2-PB9{slash}PC14-OSC32_IN)") (class "Default")
      (node (ref "U2") (pin "2") (pinfunction "PB9/PC14-OSC32_IN_2") (pintype "bidirectional"))
      (node (ref "Y1") (pin "3") (pinfunction "OUT_3") (pintype "passive"))
    )
    (net (code "32") (name "SA0") (class "Default")
      (node (ref "J2") (pin "15") (pinfunction "15_15") (pintype "passive"))
      (node (ref "R12") (pin "2") (pinfunction "2_2") (pintype "passive"))
    )
    (net (code "33") (name "SWCLK") (class "Default")
      (node (ref "J3") (pin "2") (pinfunction "2_2") (pintype "passive"))
      (node (ref "R13") (pin "1") (pinfunction "1_1") (pintype "passive"))
      (node (ref "U2") (pin "19") (pinfunction "PA15/PA14-BOOT0_19") (pintype "passive"))
    )
    (net (code "34") (name "SWDIO") (class "Default")
      (node (ref "J3") (pin "4") (pinfunction "4_4") (pintype "passive"))
      (node (ref "U2") (pin "18") (pinfunction "PA13_18") (pintype "bidirectional"))
    )
    (net (code "35") (name "unconnected-(J2-Pad7)") (class "Default")
      (node (ref "J2") (pin "7") (pinfunction "7_7") (pintype "passive+no_connect"))
    )
    (net (code "36") (name "unconnected-(J2-Pad16)") (class "Default")
      (node (ref "J2") (pin "16") (pinfunction "16_16") (pintype "passive+no_connect"))
    )
    (net (code "37") (name "unconnected-(J2-Pad17)") (class "Default")
      (node (ref "J2") (pin "17") (pinfunction "17_17") (pintype "passive+no_connect"))
    )
    (net (code "38") (name "unconnected-(J2-Pad21)") (class "Default")
      (node (ref "J2") (pin "21") (pinfunction "21_21") (pintype "passive+no_connect"))
    )
    (net (code "39") (name "unconnected-(J2-Pad22)") (class "Default")
      (node (ref "J2") (pin "22") (pinfunction "22_22") (pintype "passive+no_connect"))
    )
    (net (code "40") (name "unconnected-(J2-Pad23)") (class "Default")
      (node (ref "J2") (pin "23") (pinfunction "23_23") (pintype "passive+no_connect"))
    )
    (net (code "41") (name "unconnected-(J2-Pad24)") (class "Default")
      (node (ref "J2") (pin "24") (pinfunction "24_24") (pintype "passive+no_connect"))
    )
    (net (code "42") (name "unconnected-(J2-Pad25)") (class "Default")
      (node (ref "J2") (pin "25") (pinfunction "25_25") (pintype "passive+no_connect"))
    )
    (net (code "43") (name "unconnected-(J2-PadS1)") (class "Default")
      (node (ref "J2") (pin "S1") (pinfunction "S1_S1") (pintype "passive+no_connect"))
    )
    (net (code "44") (name "unconnected-(J2-PadS2)") (class "Default")
      (node (ref "J2") (pin "S2") (pinfunction "S2_S2") (pintype "passive+no_connect"))
    )
    (net (code "45") (name "unconnected-(J3-Pad6)") (class "Default")
      (node (ref "J3") (pin "6") (pinfunction "6_6") (pintype "passive+no_connect"))
    )
    (net (code "46") (name "unconnected-(U1-VBM-Pad10)") (class "Default")
      (node (ref "U1") (pin "10") (pinfunction "VBM_10") (pintype "passive+no_connect"))
    )
    (net (code "47") (name "unconnected-(U2-PA3-Pad10)") (class "Default")
      (node (ref "U2") (pin "10") (pinfunction "PA3_10") (pintype "bidirectional+no_connect"))
    )
    (net (code "48") (name "unconnected-(Y1-E{slash}D-Pad1)") (class "Default")
      (node (ref "Y1") (pin "1") (pinfunction "E/D_1") (pintype "passive+no_connect"))
    )
  )
)
